# W108X.net
KiCad netlist of a schematic drawn in EAGLE
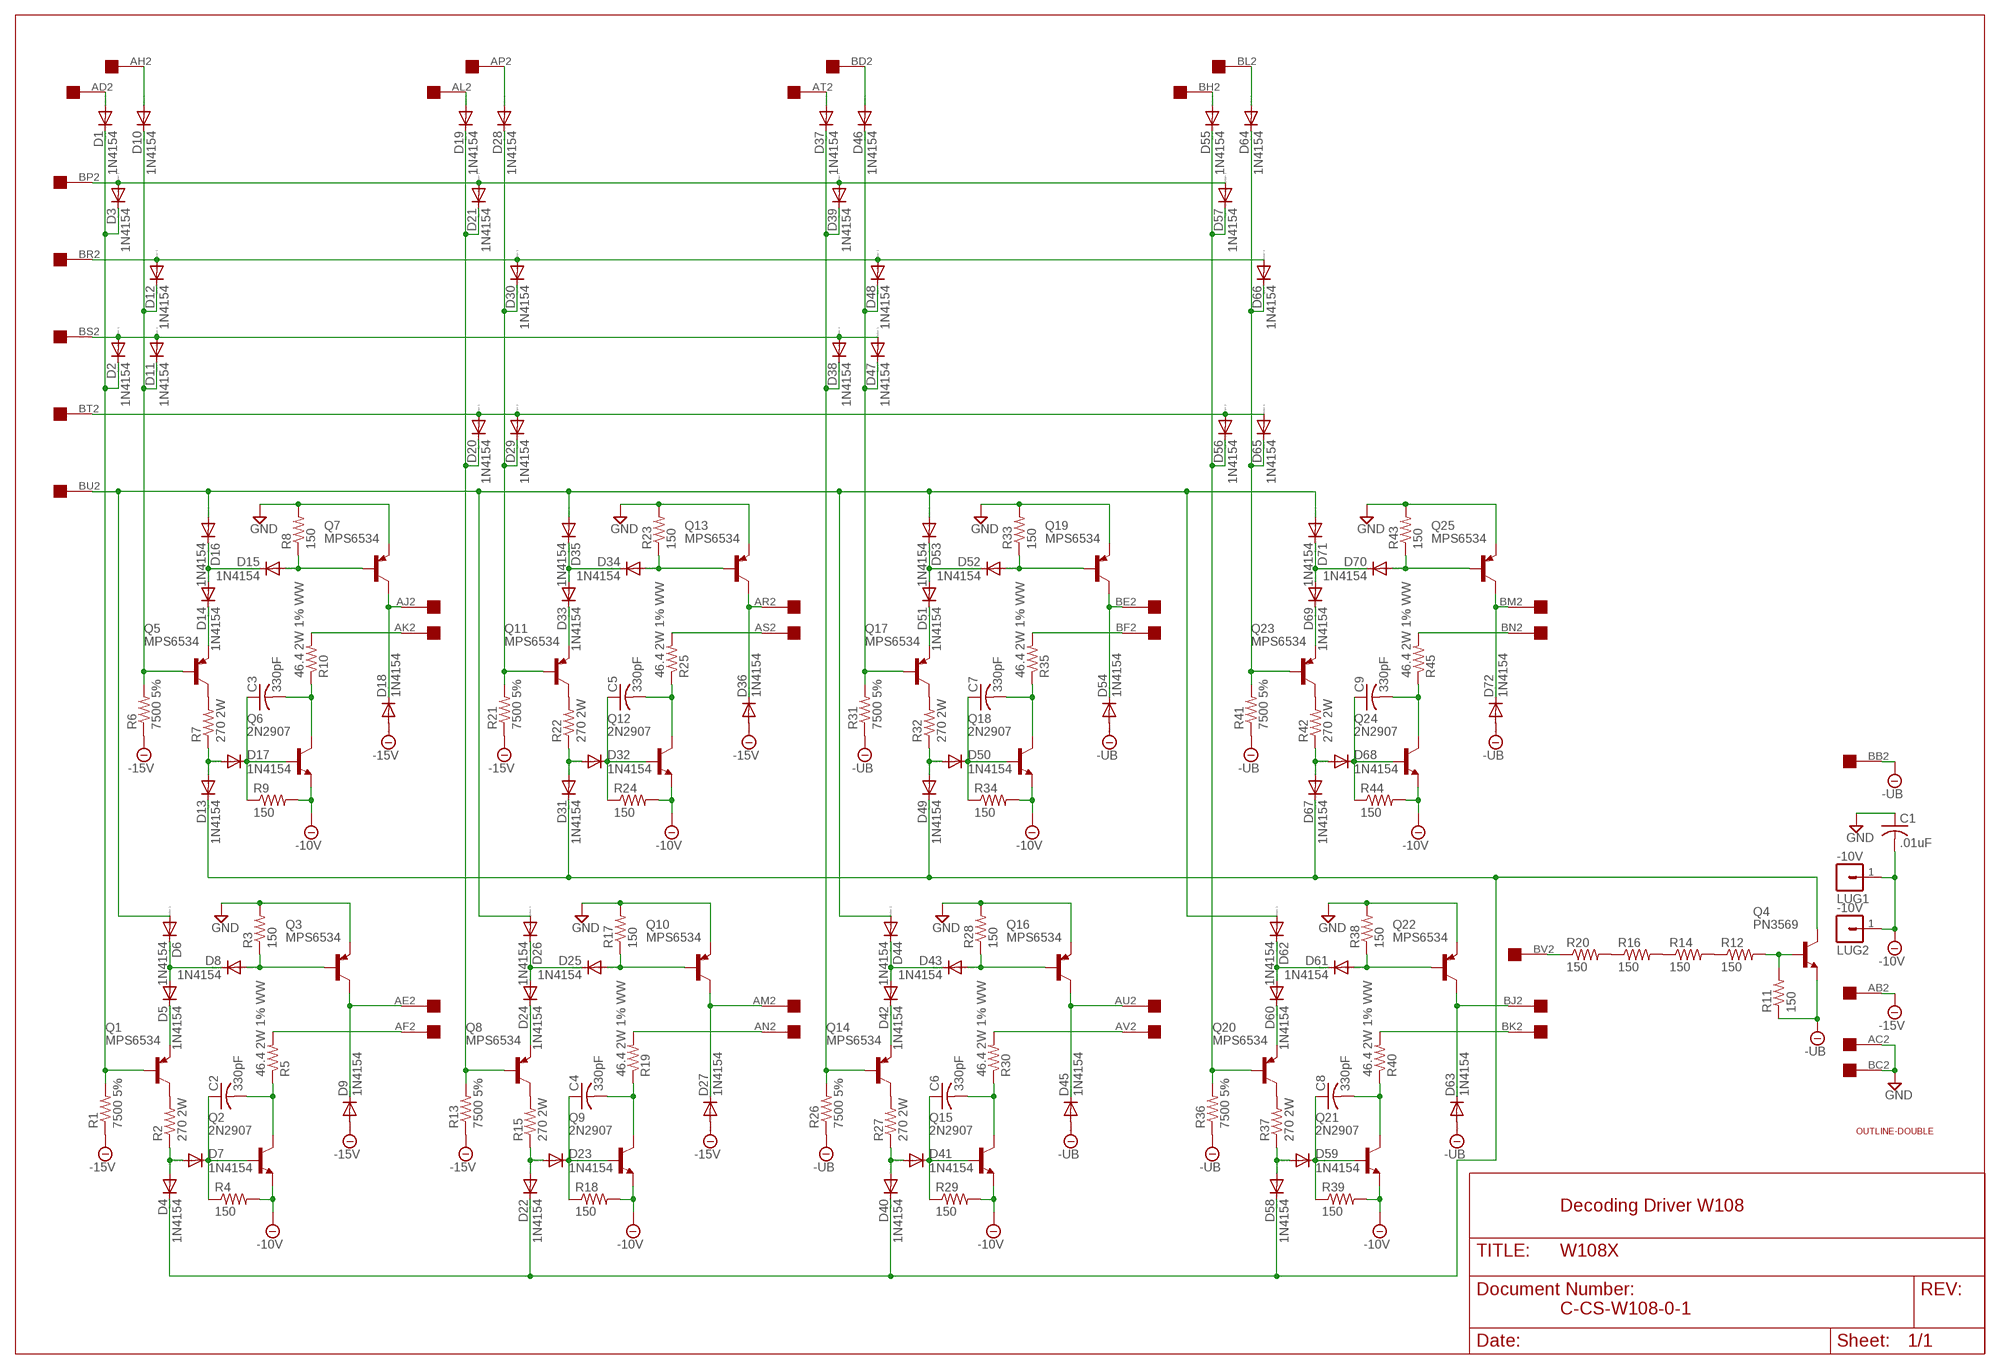
[diagram p0: schematic, sheet 1]

(export (version "E")
  (design (tool "Eeschema 10.0.6"))
  (components
    (comp (ref "C1")
      (value ".01uF")
      (footprint "eagle-import:C075-032X103")
      (libsource (lib "eagle-import") (part "C-US075-032X103"))
    )
    (comp (ref "C2")
      (value "330pF")
      (footprint "eagle-import:C075-032X103")
      (libsource (lib "eagle-import") (part "C-US075-032X103"))
    )
    (comp (ref "C3")
      (value "330pF")
      (footprint "eagle-import:C075-032X103")
      (libsource (lib "eagle-import") (part "C-US075-032X103"))
    )
    (comp (ref "C4")
      (value "330pF")
      (footprint "eagle-import:C075-032X103")
      (libsource (lib "eagle-import") (part "C-US075-032X103"))
    )
    (comp (ref "C5")
      (value "330pF")
      (footprint "eagle-import:C075-032X103")
      (libsource (lib "eagle-import") (part "C-US075-032X103"))
    )
    (comp (ref "C6")
      (value "330pF")
      (footprint "eagle-import:C075-032X103")
      (libsource (lib "eagle-import") (part "C-US075-032X103"))
    )
    (comp (ref "C7")
      (value "330pF")
      (footprint "eagle-import:C075-032X103")
      (libsource (lib "eagle-import") (part "C-US075-032X103"))
    )
    (comp (ref "C8")
      (value "330pF")
      (footprint "eagle-import:C075-032X103")
      (libsource (lib "eagle-import") (part "C-US075-032X103"))
    )
    (comp (ref "C9")
      (value "330pF")
      (footprint "eagle-import:C075-032X103")
      (libsource (lib "eagle-import") (part "C-US075-032X103"))
    )
    (comp (ref "D1")
      (value "1N4154")
      (footprint "eagle-import:DO35-10")
      (libsource (lib "eagle-import") (part "1N4148DO35-10"))
    )
    (comp (ref "D2")
      (value "1N4154")
      (footprint "eagle-import:DO35-10")
      (libsource (lib "eagle-import") (part "1N4148DO35-10"))
    )
    (comp (ref "D3")
      (value "1N4154")
      (footprint "eagle-import:DO35-10")
      (libsource (lib "eagle-import") (part "1N4148DO35-10"))
    )
    (comp (ref "D4")
      (value "1N4154")
      (footprint "eagle-import:DO35-10")
      (libsource (lib "eagle-import") (part "1N4148DO35-10"))
    )
    (comp (ref "D5")
      (value "1N4154")
      (footprint "eagle-import:DO35-10")
      (libsource (lib "eagle-import") (part "1N4148DO35-10"))
    )
    (comp (ref "D6")
      (value "1N4154")
      (footprint "eagle-import:DO35-10")
      (libsource (lib "eagle-import") (part "1N4148DO35-10"))
    )
    (comp (ref "D7")
      (value "1N4154")
      (footprint "eagle-import:DO35-10")
      (libsource (lib "eagle-import") (part "1N4148DO35-10"))
    )
    (comp (ref "D8")
      (value "1N4154")
      (footprint "eagle-import:DO35-10")
      (libsource (lib "eagle-import") (part "1N4148DO35-10"))
    )
    (comp (ref "D9")
      (value "1N4154")
      (footprint "eagle-import:DO35-10")
      (libsource (lib "eagle-import") (part "1N4148DO35-10"))
    )
    (comp (ref "D10")
      (value "1N4154")
      (footprint "eagle-import:DO35-10")
      (libsource (lib "eagle-import") (part "1N4148DO35-10"))
    )
    (comp (ref "D11")
      (value "1N4154")
      (footprint "eagle-import:DO35-10")
      (libsource (lib "eagle-import") (part "1N4148DO35-10"))
    )
    (comp (ref "D12")
      (value "1N4154")
      (footprint "eagle-import:DO35-10")
      (libsource (lib "eagle-import") (part "1N4148DO35-10"))
    )
    (comp (ref "D13")
      (value "1N4154")
      (footprint "eagle-import:DO35-10")
      (libsource (lib "eagle-import") (part "1N4148DO35-10"))
    )
    (comp (ref "D14")
      (value "1N4154")
      (footprint "eagle-import:DO35-10")
      (libsource (lib "eagle-import") (part "1N4148DO35-10"))
    )
    (comp (ref "D15")
      (value "1N4154")
      (footprint "eagle-import:DO35-10")
      (libsource (lib "eagle-import") (part "1N4148DO35-10"))
    )
    (comp (ref "D16")
      (value "1N4154")
      (footprint "eagle-import:DO35-10")
      (libsource (lib "eagle-import") (part "1N4148DO35-10"))
    )
    (comp (ref "D17")
      (value "1N4154")
      (footprint "eagle-import:DO35-10")
      (libsource (lib "eagle-import") (part "1N4148DO35-10"))
    )
    (comp (ref "D18")
      (value "1N4154")
      (footprint "eagle-import:DO35-10")
      (libsource (lib "eagle-import") (part "1N4148DO35-10"))
    )
    (comp (ref "D19")
      (value "1N4154")
      (footprint "eagle-import:DO35-10")
      (libsource (lib "eagle-import") (part "1N4148DO35-10"))
    )
    (comp (ref "D20")
      (value "1N4154")
      (footprint "eagle-import:DO35-10")
      (libsource (lib "eagle-import") (part "1N4148DO35-10"))
    )
    (comp (ref "D21")
      (value "1N4154")
      (footprint "eagle-import:DO35-10")
      (libsource (lib "eagle-import") (part "1N4148DO35-10"))
    )
    (comp (ref "D22")
      (value "1N4154")
      (footprint "eagle-import:DO35-10")
      (libsource (lib "eagle-import") (part "1N4148DO35-10"))
    )
    (comp (ref "D23")
      (value "1N4154")
      (footprint "eagle-import:DO35-10")
      (libsource (lib "eagle-import") (part "1N4148DO35-10"))
    )
    (comp (ref "D24")
      (value "1N4154")
      (footprint "eagle-import:DO35-10")
      (libsource (lib "eagle-import") (part "1N4148DO35-10"))
    )
    (comp (ref "D25")
      (value "1N4154")
      (footprint "eagle-import:DO35-10")
      (libsource (lib "eagle-import") (part "1N4148DO35-10"))
    )
    (comp (ref "D26")
      (value "1N4154")
      (footprint "eagle-import:DO35-10")
      (libsource (lib "eagle-import") (part "1N4148DO35-10"))
    )
    (comp (ref "D27")
      (value "1N4154")
      (footprint "eagle-import:DO35-10")
      (libsource (lib "eagle-import") (part "1N4148DO35-10"))
    )
    (comp (ref "D28")
      (value "1N4154")
      (footprint "eagle-import:DO35-10")
      (libsource (lib "eagle-import") (part "1N4148DO35-10"))
    )
    (comp (ref "D29")
      (value "1N4154")
      (footprint "eagle-import:DO35-10")
      (libsource (lib "eagle-import") (part "1N4148DO35-10"))
    )
    (comp (ref "D30")
      (value "1N4154")
      (footprint "eagle-import:DO35-10")
      (libsource (lib "eagle-import") (part "1N4148DO35-10"))
    )
    (comp (ref "D31")
      (value "1N4154")
      (footprint "eagle-import:DO35-10")
      (libsource (lib "eagle-import") (part "1N4148DO35-10"))
    )
    (comp (ref "D32")
      (value "1N4154")
      (footprint "eagle-import:DO35-10")
      (libsource (lib "eagle-import") (part "1N4148DO35-10"))
    )
    (comp (ref "D33")
      (value "1N4154")
      (footprint "eagle-import:DO35-10")
      (libsource (lib "eagle-import") (part "1N4148DO35-10"))
    )
    (comp (ref "D34")
      (value "1N4154")
      (footprint "eagle-import:DO35-10")
      (libsource (lib "eagle-import") (part "1N4148DO35-10"))
    )
    (comp (ref "D35")
      (value "1N4154")
      (footprint "eagle-import:DO35-10")
      (libsource (lib "eagle-import") (part "1N4148DO35-10"))
    )
    (comp (ref "D36")
      (value "1N4154")
      (footprint "eagle-import:DO35-10")
      (libsource (lib "eagle-import") (part "1N4148DO35-10"))
    )
    (comp (ref "D37")
      (value "1N4154")
      (footprint "eagle-import:DO35-10")
      (libsource (lib "eagle-import") (part "1N4148DO35-10"))
    )
    (comp (ref "D38")
      (value "1N4154")
      (footprint "eagle-import:DO35-10")
      (libsource (lib "eagle-import") (part "1N4148DO35-10"))
    )
    (comp (ref "D39")
      (value "1N4154")
      (footprint "eagle-import:DO35-10")
      (libsource (lib "eagle-import") (part "1N4148DO35-10"))
    )
    (comp (ref "D40")
      (value "1N4154")
      (footprint "eagle-import:DO35-10")
      (libsource (lib "eagle-import") (part "1N4148DO35-10"))
    )
    (comp (ref "D41")
      (value "1N4154")
      (footprint "eagle-import:DO35-10")
      (libsource (lib "eagle-import") (part "1N4148DO35-10"))
    )
    (comp (ref "D42")
      (value "1N4154")
      (footprint "eagle-import:DO35-10")
      (libsource (lib "eagle-import") (part "1N4148DO35-10"))
    )
    (comp (ref "D43")
      (value "1N4154")
      (footprint "eagle-import:DO35-10")
      (libsource (lib "eagle-import") (part "1N4148DO35-10"))
    )
    (comp (ref "D44")
      (value "1N4154")
      (footprint "eagle-import:DO35-10")
      (libsource (lib "eagle-import") (part "1N4148DO35-10"))
    )
    (comp (ref "D45")
      (value "1N4154")
      (footprint "eagle-import:DO35-10")
      (libsource (lib "eagle-import") (part "1N4148DO35-10"))
    )
    (comp (ref "D46")
      (value "1N4154")
      (footprint "eagle-import:DO35-10")
      (libsource (lib "eagle-import") (part "1N4148DO35-10"))
    )
    (comp (ref "D47")
      (value "1N4154")
      (footprint "eagle-import:DO35-10")
      (libsource (lib "eagle-import") (part "1N4148DO35-10"))
    )
    (comp (ref "D48")
      (value "1N4154")
      (footprint "eagle-import:DO35-10")
      (libsource (lib "eagle-import") (part "1N4148DO35-10"))
    )
    (comp (ref "D49")
      (value "1N4154")
      (footprint "eagle-import:DO35-10")
      (libsource (lib "eagle-import") (part "1N4148DO35-10"))
    )
    (comp (ref "D50")
      (value "1N4154")
      (footprint "eagle-import:DO35-10")
      (libsource (lib "eagle-import") (part "1N4148DO35-10"))
    )
    (comp (ref "D51")
      (value "1N4154")
      (footprint "eagle-import:DO35-10")
      (libsource (lib "eagle-import") (part "1N4148DO35-10"))
    )
    (comp (ref "D52")
      (value "1N4154")
      (footprint "eagle-import:DO35-10")
      (libsource (lib "eagle-import") (part "1N4148DO35-10"))
    )
    (comp (ref "D53")
      (value "1N4154")
      (footprint "eagle-import:DO35-10")
      (libsource (lib "eagle-import") (part "1N4148DO35-10"))
    )
    (comp (ref "D54")
      (value "1N4154")
      (footprint "eagle-import:DO35-10")
      (libsource (lib "eagle-import") (part "1N4148DO35-10"))
    )
    (comp (ref "D55")
      (value "1N4154")
      (footprint "eagle-import:DO35-10")
      (libsource (lib "eagle-import") (part "1N4148DO35-10"))
    )
    (comp (ref "D56")
      (value "1N4154")
      (footprint "eagle-import:DO35-10")
      (libsource (lib "eagle-import") (part "1N4148DO35-10"))
    )
    (comp (ref "D57")
      (value "1N4154")
      (footprint "eagle-import:DO35-10")
      (libsource (lib "eagle-import") (part "1N4148DO35-10"))
    )
    (comp (ref "D58")
      (value "1N4154")
      (footprint "eagle-import:DO35-10")
      (libsource (lib "eagle-import") (part "1N4148DO35-10"))
    )
    (comp (ref "D59")
      (value "1N4154")
      (footprint "eagle-import:DO35-10")
      (libsource (lib "eagle-import") (part "1N4148DO35-10"))
    )
    (comp (ref "D60")
      (value "1N4154")
      (footprint "eagle-import:DO35-10")
      (libsource (lib "eagle-import") (part "1N4148DO35-10"))
    )
    (comp (ref "D61")
      (value "1N4154")
      (footprint "eagle-import:DO35-10")
      (libsource (lib "eagle-import") (part "1N4148DO35-10"))
    )
    (comp (ref "D62")
      (value "1N4154")
      (footprint "eagle-import:DO35-10")
      (libsource (lib "eagle-import") (part "1N4148DO35-10"))
    )
    (comp (ref "D63")
      (value "1N4154")
      (footprint "eagle-import:DO35-10")
      (libsource (lib "eagle-import") (part "1N4148DO35-10"))
    )
    (comp (ref "D64")
      (value "1N4154")
      (footprint "eagle-import:DO35-10")
      (libsource (lib "eagle-import") (part "1N4148DO35-10"))
    )
    (comp (ref "D65")
      (value "1N4154")
      (footprint "eagle-import:DO35-10")
      (libsource (lib "eagle-import") (part "1N4148DO35-10"))
    )
    (comp (ref "D66")
      (value "1N4154")
      (footprint "eagle-import:DO35-10")
      (libsource (lib "eagle-import") (part "1N4148DO35-10"))
    )
    (comp (ref "D67")
      (value "1N4154")
      (footprint "eagle-import:DO35-10")
      (libsource (lib "eagle-import") (part "1N4148DO35-10"))
    )
    (comp (ref "D68")
      (value "1N4154")
      (footprint "eagle-import:DO35-10")
      (libsource (lib "eagle-import") (part "1N4148DO35-10"))
    )
    (comp (ref "D69")
      (value "1N4154")
      (footprint "eagle-import:DO35-10")
      (libsource (lib "eagle-import") (part "1N4148DO35-10"))
    )
    (comp (ref "D70")
      (value "1N4154")
      (footprint "eagle-import:DO35-10")
      (libsource (lib "eagle-import") (part "1N4148DO35-10"))
    )
    (comp (ref "D71")
      (value "1N4154")
      (footprint "eagle-import:DO35-10")
      (libsource (lib "eagle-import") (part "1N4148DO35-10"))
    )
    (comp (ref "D72")
      (value "1N4154")
      (footprint "eagle-import:DO35-10")
      (libsource (lib "eagle-import") (part "1N4148DO35-10"))
    )
    (comp (ref "LUG1")
      (value "-10V")
      (footprint "eagle-import:SPADELUG")
      (libsource (lib "eagle-import") (part "LUG"))
    )
    (comp (ref "LUG2")
      (value "-10V")
      (footprint "eagle-import:SPADELUG")
      (libsource (lib "eagle-import") (part "LUG"))
    )
    (comp (ref "Q1")
      (value "MPS6534")
      (footprint "eagle-import:TO39")
      (libsource (lib "eagle-import") (part "2N2904"))
    )
    (comp (ref "Q2")
      (value "2N2907")
      (footprint "eagle-import:TO5")
      (libsource (lib "eagle-import") (part "2N2102"))
    )
    (comp (ref "Q3")
      (value "MPS6534")
      (footprint "eagle-import:TO39")
      (libsource (lib "eagle-import") (part "2N2904"))
    )
    (comp (ref "Q4")
      (value "PN3569")
      (footprint "eagle-import:TO5")
      (libsource (lib "eagle-import") (part "2N2102"))
    )
    (comp (ref "Q5")
      (value "MPS6534")
      (footprint "eagle-import:TO39")
      (libsource (lib "eagle-import") (part "2N2904"))
    )
    (comp (ref "Q6")
      (value "2N2907")
      (footprint "eagle-import:TO5")
      (libsource (lib "eagle-import") (part "2N2102"))
    )
    (comp (ref "Q7")
      (value "MPS6534")
      (footprint "eagle-import:TO39")
      (libsource (lib "eagle-import") (part "2N2904"))
    )
    (comp (ref "Q8")
      (value "MPS6534")
      (footprint "eagle-import:TO39")
      (libsource (lib "eagle-import") (part "2N2904"))
    )
    (comp (ref "Q9")
      (value "2N2907")
      (footprint "eagle-import:TO5")
      (libsource (lib "eagle-import") (part "2N2102"))
    )
    (comp (ref "Q10")
      (value "MPS6534")
      (footprint "eagle-import:TO39")
      (libsource (lib "eagle-import") (part "2N2904"))
    )
    (comp (ref "Q11")
      (value "MPS6534")
      (footprint "eagle-import:TO39")
      (libsource (lib "eagle-import") (part "2N2904"))
    )
    (comp (ref "Q12")
      (value "2N2907")
      (footprint "eagle-import:TO5")
      (libsource (lib "eagle-import") (part "2N2102"))
    )
    (comp (ref "Q13")
      (value "MPS6534")
      (footprint "eagle-import:TO39")
      (libsource (lib "eagle-import") (part "2N2904"))
    )
    (comp (ref "Q14")
      (value "MPS6534")
      (footprint "eagle-import:TO39")
      (libsource (lib "eagle-import") (part "2N2904"))
    )
    (comp (ref "Q15")
      (value "2N2907")
      (footprint "eagle-import:TO5")
      (libsource (lib "eagle-import") (part "2N2102"))
    )
    (comp (ref "Q16")
      (value "MPS6534")
      (footprint "eagle-import:TO39")
      (libsource (lib "eagle-import") (part "2N2904"))
    )
    (comp (ref "Q17")
      (value "MPS6534")
      (footprint "eagle-import:TO39")
      (libsource (lib "eagle-import") (part "2N2904"))
    )
    (comp (ref "Q18")
      (value "2N2907")
      (footprint "eagle-import:TO5")
      (libsource (lib "eagle-import") (part "2N2102"))
    )
    (comp (ref "Q19")
      (value "MPS6534")
      (footprint "eagle-import:TO39")
      (libsource (lib "eagle-import") (part "2N2904"))
    )
    (comp (ref "Q20")
      (value "MPS6534")
      (footprint "eagle-import:TO39")
      (libsource (lib "eagle-import") (part "2N2904"))
    )
    (comp (ref "Q21")
      (value "2N2907")
      (footprint "eagle-import:TO5")
      (libsource (lib "eagle-import") (part "2N2102"))
    )
    (comp (ref "Q22")
      (value "MPS6534")
      (footprint "eagle-import:TO39")
      (libsource (lib "eagle-import") (part "2N2904"))
    )
    (comp (ref "Q23")
      (value "MPS6534")
      (footprint "eagle-import:TO39")
      (libsource (lib "eagle-import") (part "2N2904"))
    )
    (comp (ref "Q24")
      (value "2N2907")
      (footprint "eagle-import:TO5")
      (libsource (lib "eagle-import") (part "2N2102"))
    )
    (comp (ref "Q25")
      (value "MPS6534")
      (footprint "eagle-import:TO39")
      (libsource (lib "eagle-import") (part "2N2904"))
    )
    (comp (ref "R1")
      (value "7500 5%")
      (footprint "eagle-import:0207_10")
      (libsource (lib "eagle-import") (part "R-US_0207/10"))
    )
    (comp (ref "R2")
      (value "270 2W")
      (footprint "eagle-import:0617_22")
      (libsource (lib "eagle-import") (part "R-US_0617/22"))
    )
    (comp (ref "R3")
      (value "150")
      (footprint "eagle-import:0207_10")
      (libsource (lib "eagle-import") (part "R-US_0207/10"))
    )
    (comp (ref "R4")
      (value "150")
      (footprint "eagle-import:0207_10")
      (libsource (lib "eagle-import") (part "R-US_0207/10"))
    )
    (comp (ref "R5")
      (value "46.4 2W 1% WW")
      (footprint "eagle-import:0414_20")
      (libsource (lib "eagle-import") (part "R-US_0414/20"))
    )
    (comp (ref "R6")
      (value "7500 5%")
      (footprint "eagle-import:0207_10")
      (libsource (lib "eagle-import") (part "R-US_0207/10"))
    )
    (comp (ref "R7")
      (value "270 2W")
      (footprint "eagle-import:0617_22")
      (libsource (lib "eagle-import") (part "R-US_0617/22"))
    )
    (comp (ref "R8")
      (value "150")
      (footprint "eagle-import:0207_10")
      (libsource (lib "eagle-import") (part "R-US_0207/10"))
    )
    (comp (ref "R9")
      (value "150")
      (footprint "eagle-import:0207_10")
      (libsource (lib "eagle-import") (part "R-US_0207/10"))
    )
    (comp (ref "R10")
      (value "46.4 2W 1% WW")
      (footprint "eagle-import:0414_20")
      (libsource (lib "eagle-import") (part "R-US_0414/20"))
    )
    (comp (ref "R11")
      (value "150")
      (footprint "eagle-import:0207_10")
      (libsource (lib "eagle-import") (part "R-US_0207/10"))
    )
    (comp (ref "R12")
      (value "150")
      (footprint "eagle-import:0207_10")
      (libsource (lib "eagle-import") (part "R-US_0207/10"))
    )
    (comp (ref "R13")
      (value "7500 5%")
      (footprint "eagle-import:0207_10")
      (libsource (lib "eagle-import") (part "R-US_0207/10"))
    )
    (comp (ref "R14")
      (value "150")
      (footprint "eagle-import:0207_10")
      (libsource (lib "eagle-import") (part "R-US_0207/10"))
    )
    (comp (ref "R15")
      (value "270 2W")
      (footprint "eagle-import:0617_22")
      (libsource (lib "eagle-import") (part "R-US_0617/22"))
    )
    (comp (ref "R16")
      (value "150")
      (footprint "eagle-import:0207_10")
      (libsource (lib "eagle-import") (part "R-US_0207/10"))
    )
    (comp (ref "R17")
      (value "150")
      (footprint "eagle-import:0207_10")
      (libsource (lib "eagle-import") (part "R-US_0207/10"))
    )
    (comp (ref "R18")
      (value "150")
      (footprint "eagle-import:0207_10")
      (libsource (lib "eagle-import") (part "R-US_0207/10"))
    )
    (comp (ref "R19")
      (value "46.4 2W 1% WW")
      (footprint "eagle-import:0414_20")
      (libsource (lib "eagle-import") (part "R-US_0414/20"))
    )
    (comp (ref "R20")
      (value "150")
      (footprint "eagle-import:0207_10")
      (libsource (lib "eagle-import") (part "R-US_0207/10"))
    )
    (comp (ref "R21")
      (value "7500 5%")
      (footprint "eagle-import:0207_10")
      (libsource (lib "eagle-import") (part "R-US_0207/10"))
    )
    (comp (ref "R22")
      (value "270 2W")
      (footprint "eagle-import:0617_22")
      (libsource (lib "eagle-import") (part "R-US_0617/22"))
    )
    (comp (ref "R23")
      (value "150")
      (footprint "eagle-import:0207_10")
      (libsource (lib "eagle-import") (part "R-US_0207/10"))
    )
    (comp (ref "R24")
      (value "150")
      (footprint "eagle-import:0207_10")
      (libsource (lib "eagle-import") (part "R-US_0207/10"))
    )
    (comp (ref "R25")
      (value "46.4 2W 1% WW")
      (footprint "eagle-import:0414_20")
      (libsource (lib "eagle-import") (part "R-US_0414/20"))
    )
    (comp (ref "R26")
      (value "7500 5%")
      (footprint "eagle-import:0207_10")
      (libsource (lib "eagle-import") (part "R-US_0207/10"))
    )
    (comp (ref "R27")
      (value "270 2W")
      (footprint "eagle-import:0617_22")
      (libsource (lib "eagle-import") (part "R-US_0617/22"))
    )
    (comp (ref "R28")
      (value "150")
      (footprint "eagle-import:0207_10")
      (libsource (lib "eagle-import") (part "R-US_0207/10"))
    )
    (comp (ref "R29")
      (value "150")
      (footprint "eagle-import:0207_10")
      (libsource (lib "eagle-import") (part "R-US_0207/10"))
    )
    (comp (ref "R30")
      (value "46.4 2W 1% WW")
      (footprint "eagle-import:0414_20")
      (libsource (lib "eagle-import") (part "R-US_0414/20"))
    )
    (comp (ref "R31")
      (value "7500 5%")
      (footprint "eagle-import:0207_10")
      (libsource (lib "eagle-import") (part "R-US_0207/10"))
    )
    (comp (ref "R32")
      (value "270 2W")
      (footprint "eagle-import:0617_22")
      (libsource (lib "eagle-import") (part "R-US_0617/22"))
    )
    (comp (ref "R33")
      (value "150")
      (footprint "eagle-import:0207_10")
      (libsource (lib "eagle-import") (part "R-US_0207/10"))
    )
    (comp (ref "R34")
      (value "150")
      (footprint "eagle-import:0207_10")
      (libsource (lib "eagle-import") (part "R-US_0207/10"))
    )
    (comp (ref "R35")
      (value "46.4 2W 1% WW")
      (footprint "eagle-import:0414_20")
      (libsource (lib "eagle-import") (part "R-US_0414/20"))
    )
    (comp (ref "R36")
      (value "7500 5%")
      (footprint "eagle-import:0207_10")
      (libsource (lib "eagle-import") (part "R-US_0207/10"))
    )
    (comp (ref "R37")
      (value "270 2W")
      (footprint "eagle-import:0617_22")
      (libsource (lib "eagle-import") (part "R-US_0617/22"))
    )
    (comp (ref "R38")
      (value "150")
      (footprint "eagle-import:0207_10")
      (libsource (lib "eagle-import") (part "R-US_0207/10"))
    )
    (comp (ref "R39")
      (value "150")
      (footprint "eagle-import:0207_10")
      (libsource (lib "eagle-import") (part "R-US_0207/10"))
    )
    (comp (ref "R40")
      (value "46.4 2W 1% WW")
      (footprint "eagle-import:0414_20")
      (libsource (lib "eagle-import") (part "R-US_0414/20"))
    )
    (comp (ref "R41")
      (value "7500 5%")
      (footprint "eagle-import:0207_10")
      (libsource (lib "eagle-import") (part "R-US_0207/10"))
    )
    (comp (ref "R42")
      (value "270 2W")
      (footprint "eagle-import:0617_22")
      (libsource (lib "eagle-import") (part "R-US_0617/22"))
    )
    (comp (ref "R43")
      (value "150")
      (footprint "eagle-import:0207_10")
      (libsource (lib "eagle-import") (part "R-US_0207/10"))
    )
    (comp (ref "R44")
      (value "150")
      (footprint "eagle-import:0207_10")
      (libsource (lib "eagle-import") (part "R-US_0207/10"))
    )
    (comp (ref "R45")
      (value "46.4 2W 1% WW")
      (footprint "eagle-import:0414_20")
      (libsource (lib "eagle-import") (part "R-US_0414/20"))
    )
    (comp (ref "U$1")
      (value "OUTLINE-DOUBLE")
      (footprint "eagle-import:DOUBLE")
      (libsource (lib "eagle-import") (part "OUTLINE-DOUBLE"))
    )
    (comp (ref "U$2")
      (value "DOUBLE")
      (footprint "eagle-import:EDGE-CON4")
      (libsource (lib "eagle-import") (part "DOUBLE"))
    )
  )
  (nets
    (net (code "1") (name "-10V") (class "Default")
      (node (ref "C1") (pin "2") (pinfunction "2_2") (pintype "passive"))
      (node (ref "LUG1") (pin "1") (pinfunction "1_1") (pintype "passive"))
      (node (ref "LUG2") (pin "1") (pinfunction "1_1") (pintype "passive"))
      (node (ref "Q12") (pin "1") (pinfunction "E_1") (pintype "passive"))
      (node (ref "Q15") (pin "1") (pinfunction "E_1") (pintype "passive"))
      (node (ref "Q18") (pin "1") (pinfunction "E_1") (pintype "passive"))
      (node (ref "Q2") (pin "1") (pinfunction "E_1") (pintype "passive"))
      (node (ref "Q21") (pin "1") (pinfunction "E_1") (pintype "passive"))
      (node (ref "Q24") (pin "1") (pinfunction "E_1") (pintype "passive"))
      (node (ref "Q6") (pin "1") (pinfunction "E_1") (pintype "passive"))
      (node (ref "Q9") (pin "1") (pinfunction "E_1") (pintype "passive"))
      (node (ref "R18") (pin "2") (pinfunction "2_2") (pintype "passive"))
      (node (ref "R24") (pin "2") (pinfunction "2_2") (pintype "passive"))
      (node (ref "R29") (pin "2") (pinfunction "2_2") (pintype "passive"))
      (node (ref "R34") (pin "2") (pinfunction "2_2") (pintype "passive"))
      (node (ref "R39") (pin "2") (pinfunction "2_2") (pintype "passive"))
      (node (ref "R4") (pin "2") (pinfunction "2_2") (pintype "passive"))
      (node (ref "R44") (pin "2") (pinfunction "2_2") (pintype "passive"))
      (node (ref "R9") (pin "2") (pinfunction "2_2") (pintype "passive"))
    )
    (net (code "2") (name "-15V") (class "Default")
      (node (ref "D18") (pin "A") (pinfunction "A_A") (pintype "passive"))
      (node (ref "D27") (pin "A") (pinfunction "A_A") (pintype "passive"))
      (node (ref "D36") (pin "A") (pinfunction "A_A") (pintype "passive"))
      (node (ref "D9") (pin "A") (pinfunction "A_A") (pintype "passive"))
      (node (ref "R1") (pin "1") (pinfunction "1_1") (pintype "passive"))
      (node (ref "R13") (pin "1") (pinfunction "1_1") (pintype "passive"))
      (node (ref "R21") (pin "1") (pinfunction "1_1") (pintype "passive"))
      (node (ref "R6") (pin "1") (pinfunction "1_1") (pintype "passive"))
      (node (ref "U$2") (pin "AB2") (pinfunction "1_AB2") (pintype "bidirectional"))
    )
    (net (code "3") (name "-UB") (class "Default")
      (node (ref "D45") (pin "A") (pinfunction "A_A") (pintype "passive"))
      (node (ref "D54") (pin "A") (pinfunction "A_A") (pintype "passive"))
      (node (ref "D63") (pin "A") (pinfunction "A_A") (pintype "passive"))
      (node (ref "D72") (pin "A") (pinfunction "A_A") (pintype "passive"))
      (node (ref "Q4") (pin "1") (pinfunction "E_1") (pintype "passive"))
      (node (ref "R11") (pin "1") (pinfunction "1_1") (pintype "passive"))
      (node (ref "R26") (pin "1") (pinfunction "1_1") (pintype "passive"))
      (node (ref "R31") (pin "1") (pinfunction "1_1") (pintype "passive"))
      (node (ref "R36") (pin "1") (pinfunction "1_1") (pintype "passive"))
      (node (ref "R41") (pin "1") (pinfunction "1_1") (pintype "passive"))
      (node (ref "U$2") (pin "BB2") (pinfunction "1_BB2") (pintype "bidirectional"))
    )
    (net (code "4") (name "GND") (class "Default")
      (node (ref "C1") (pin "1") (pinfunction "1_1") (pintype "passive"))
      (node (ref "Q10") (pin "1") (pinfunction "E_1") (pintype "passive"))
      (node (ref "Q13") (pin "1") (pinfunction "E_1") (pintype "passive"))
      (node (ref "Q16") (pin "1") (pinfunction "E_1") (pintype "passive"))
      (node (ref "Q19") (pin "1") (pinfunction "E_1") (pintype "passive"))
      (node (ref "Q22") (pin "1") (pinfunction "E_1") (pintype "passive"))
      (node (ref "Q25") (pin "1") (pinfunction "E_1") (pintype "passive"))
      (node (ref "Q3") (pin "1") (pinfunction "E_1") (pintype "passive"))
      (node (ref "Q7") (pin "1") (pinfunction "E_1") (pintype "passive"))
      (node (ref "R17") (pin "2") (pinfunction "2_2") (pintype "passive"))
      (node (ref "R23") (pin "2") (pinfunction "2_2") (pintype "passive"))
      (node (ref "R28") (pin "2") (pinfunction "2_2") (pintype "passive"))
      (node (ref "R3") (pin "2") (pinfunction "2_2") (pintype "passive"))
      (node (ref "R33") (pin "2") (pinfunction "2_2") (pintype "passive"))
      (node (ref "R38") (pin "2") (pinfunction "2_2") (pintype "passive"))
      (node (ref "R43") (pin "2") (pinfunction "2_2") (pintype "passive"))
      (node (ref "R8") (pin "2") (pinfunction "2_2") (pintype "passive"))
      (node (ref "U$2") (pin "AC2") (pinfunction "1_AC2") (pintype "bidirectional"))
      (node (ref "U$2") (pin "BC2") (pinfunction "1_BC2") (pintype "bidirectional"))
    )
    (net (code "5") (name "Net-(D4-PadA)") (class "Default")
      (node (ref "D4") (pin "A") (pinfunction "A_A") (pintype "passive"))
      (node (ref "D7") (pin "A") (pinfunction "A_A") (pintype "passive"))
      (node (ref "R2") (pin "1") (pinfunction "1_1") (pintype "passive"))
    )
    (net (code "6") (name "Net-(D5-PadA)") (class "Default")
      (node (ref "D5") (pin "A") (pinfunction "A_A") (pintype "passive"))
      (node (ref "D6") (pin "C") (pinfunction "C_C") (pintype "passive"))
      (node (ref "D8") (pin "C") (pinfunction "C_C") (pintype "passive"))
    )
    (net (code "7") (name "Net-(D13-PadA)") (class "Default")
      (node (ref "D13") (pin "A") (pinfunction "A_A") (pintype "passive"))
      (node (ref "D17") (pin "A") (pinfunction "A_A") (pintype "passive"))
      (node (ref "R7") (pin "1") (pinfunction "1_1") (pintype "passive"))
    )
    (net (code "8") (name "Net-(D14-PadA)") (class "Default")
      (node (ref "D14") (pin "A") (pinfunction "A_A") (pintype "passive"))
      (node (ref "D15") (pin "C") (pinfunction "C_C") (pintype "passive"))
      (node (ref "D16") (pin "C") (pinfunction "C_C") (pintype "passive"))
    )
    (net (code "9") (name "Net-(D22-PadA)") (class "Default")
      (node (ref "D22") (pin "A") (pinfunction "A_A") (pintype "passive"))
      (node (ref "D23") (pin "A") (pinfunction "A_A") (pintype "passive"))
      (node (ref "R15") (pin "1") (pinfunction "1_1") (pintype "passive"))
    )
    (net (code "10") (name "Net-(D24-PadA)") (class "Default")
      (node (ref "D24") (pin "A") (pinfunction "A_A") (pintype "passive"))
      (node (ref "D25") (pin "C") (pinfunction "C_C") (pintype "passive"))
      (node (ref "D26") (pin "C") (pinfunction "C_C") (pintype "passive"))
    )
    (net (code "11") (name "Net-(D31-PadA)") (class "Default")
      (node (ref "D31") (pin "A") (pinfunction "A_A") (pintype "passive"))
      (node (ref "D32") (pin "A") (pinfunction "A_A") (pintype "passive"))
      (node (ref "R22") (pin "1") (pinfunction "1_1") (pintype "passive"))
    )
    (net (code "12") (name "Net-(D33-PadA)") (class "Default")
      (node (ref "D33") (pin "A") (pinfunction "A_A") (pintype "passive"))
      (node (ref "D34") (pin "C") (pinfunction "C_C") (pintype "passive"))
      (node (ref "D35") (pin "C") (pinfunction "C_C") (pintype "passive"))
    )
    (net (code "13") (name "Net-(D40-PadA)") (class "Default")
      (node (ref "D40") (pin "A") (pinfunction "A_A") (pintype "passive"))
      (node (ref "D41") (pin "A") (pinfunction "A_A") (pintype "passive"))
      (node (ref "R27") (pin "1") (pinfunction "1_1") (pintype "passive"))
    )
    (net (code "14") (name "Net-(D42-PadA)") (class "Default")
      (node (ref "D42") (pin "A") (pinfunction "A_A") (pintype "passive"))
      (node (ref "D43") (pin "C") (pinfunction "C_C") (pintype "passive"))
      (node (ref "D44") (pin "C") (pinfunction "C_C") (pintype "passive"))
    )
    (net (code "15") (name "Net-(D49-PadA)") (class "Default")
      (node (ref "D49") (pin "A") (pinfunction "A_A") (pintype "passive"))
      (node (ref "D50") (pin "A") (pinfunction "A_A") (pintype "passive"))
      (node (ref "R32") (pin "1") (pinfunction "1_1") (pintype "passive"))
    )
    (net (code "16") (name "Net-(D51-PadA)") (class "Default")
      (node (ref "D51") (pin "A") (pinfunction "A_A") (pintype "passive"))
      (node (ref "D52") (pin "C") (pinfunction "C_C") (pintype "passive"))
      (node (ref "D53") (pin "C") (pinfunction "C_C") (pintype "passive"))
    )
    (net (code "17") (name "Net-(D58-PadA)") (class "Default")
      (node (ref "D58") (pin "A") (pinfunction "A_A") (pintype "passive"))
      (node (ref "D59") (pin "A") (pinfunction "A_A") (pintype "passive"))
      (node (ref "R37") (pin "1") (pinfunction "1_1") (pintype "passive"))
    )
    (net (code "18") (name "Net-(D60-PadA)") (class "Default")
      (node (ref "D60") (pin "A") (pinfunction "A_A") (pintype "passive"))
      (node (ref "D61") (pin "C") (pinfunction "C_C") (pintype "passive"))
      (node (ref "D62") (pin "C") (pinfunction "C_C") (pintype "passive"))
    )
    (net (code "19") (name "Net-(D67-PadA)") (class "Default")
      (node (ref "D67") (pin "A") (pinfunction "A_A") (pintype "passive"))
      (node (ref "D68") (pin "A") (pinfunction "A_A") (pintype "passive"))
      (node (ref "R42") (pin "1") (pinfunction "1_1") (pintype "passive"))
    )
    (net (code "20") (name "Net-(D69-PadA)") (class "Default")
      (node (ref "D69") (pin "A") (pinfunction "A_A") (pintype "passive"))
      (node (ref "D70") (pin "C") (pinfunction "C_C") (pintype "passive"))
      (node (ref "D71") (pin "C") (pinfunction "C_C") (pintype "passive"))
    )
    (net (code "21") (name "Net-(Q1-B)") (class "Default")
      (node (ref "D1") (pin "C") (pinfunction "C_C") (pintype "passive"))
      (node (ref "D2") (pin "C") (pinfunction "C_C") (pintype "passive"))
      (node (ref "D3") (pin "C") (pinfunction "C_C") (pintype "passive"))
      (node (ref "Q1") (pin "2") (pinfunction "B_2") (pintype "passive"))
      (node (ref "R1") (pin "2") (pinfunction "2_2") (pintype "passive"))
    )
    (net (code "22") (name "Net-(Q1-C)") (class "Default")
      (node (ref "Q1") (pin "3") (pinfunction "C_3") (pintype "passive"))
      (node (ref "R2") (pin "2") (pinfunction "2_2") (pintype "passive"))
    )
    (net (code "23") (name "Net-(Q1-E)") (class "Default")
      (node (ref "D5") (pin "C") (pinfunction "C_C") (pintype "passive"))
      (node (ref "Q1") (pin "1") (pinfunction "E_1") (pintype "passive"))
    )
    (net (code "24") (name "Net-(Q2-B)") (class "Default")
      (node (ref "C2") (pin "1") (pinfunction "1_1") (pintype "passive"))
      (node (ref "D7") (pin "C") (pinfunction "C_C") (pintype "passive"))
      (node (ref "Q2") (pin "2") (pinfunction "B_2") (pintype "passive"))
      (node (ref "R4") (pin "1") (pinfunction "1_1") (pintype "passive"))
    )
    (net (code "25") (name "Net-(Q2-C)") (class "Default")
      (node (ref "C2") (pin "2") (pinfunction "2_2") (pintype "passive"))
      (node (ref "Q2") (pin "3") (pinfunction "C_3") (pintype "passive"))
      (node (ref "R5") (pin "1") (pinfunction "1_1") (pintype "passive"))
    )
    (net (code "26") (name "Net-(Q3-B)") (class "Default")
      (node (ref "D8") (pin "A") (pinfunction "A_A") (pintype "passive"))
      (node (ref "Q3") (pin "2") (pinfunction "B_2") (pintype "passive"))
      (node (ref "R3") (pin "1") (pinfunction "1_1") (pintype "passive"))
    )
    (net (code "27") (name "Net-(Q3-C)") (class "Default")
      (node (ref "D9") (pin "C") (pinfunction "C_C") (pintype "passive"))
      (node (ref "Q3") (pin "3") (pinfunction "C_3") (pintype "passive"))
      (node (ref "U$2") (pin "AE2") (pinfunction "1_AE2") (pintype "bidirectional"))
    )
    (net (code "28") (name "Net-(Q4-B)") (class "Default")
      (node (ref "Q4") (pin "2") (pinfunction "B_2") (pintype "passive"))
      (node (ref "R11") (pin "2") (pinfunction "2_2") (pintype "passive"))
      (node (ref "R12") (pin "2") (pinfunction "2_2") (pintype "passive"))
    )
    (net (code "29") (name "Net-(Q4-C)") (class "Default")
      (node (ref "D13") (pin "C") (pinfunction "C_C") (pintype "passive"))
      (node (ref "D22") (pin "C") (pinfunction "C_C") (pintype "passive"))
      (node (ref "D31") (pin "C") (pinfunction "C_C") (pintype "passive"))
      (node (ref "D4") (pin "C") (pinfunction "C_C") (pintype "passive"))
      (node (ref "D40") (pin "C") (pinfunction "C_C") (pintype "passive"))
      (node (ref "D49") (pin "C") (pinfunction "C_C") (pintype "passive"))
      (node (ref "D58") (pin "C") (pinfunction "C_C") (pintype "passive"))
      (node (ref "D67") (pin "C") (pinfunction "C_C") (pintype "passive"))
      (node (ref "Q4") (pin "3") (pinfunction "C_3") (pintype "passive"))
    )
    (net (code "30") (name "Net-(Q5-B)") (class "Default")
      (node (ref "D10") (pin "C") (pinfunction "C_C") (pintype "passive"))
      (node (ref "D11") (pin "C") (pinfunction "C_C") (pintype "passive"))
      (node (ref "D12") (pin "C") (pinfunction "C_C") (pintype "passive"))
      (node (ref "Q5") (pin "2") (pinfunction "B_2") (pintype "passive"))
      (node (ref "R6") (pin "2") (pinfunction "2_2") (pintype "passive"))
    )
    (net (code "31") (name "Net-(Q5-C)") (class "Default")
      (node (ref "Q5") (pin "3") (pinfunction "C_3") (pintype "passive"))
      (node (ref "R7") (pin "2") (pinfunction "2_2") (pintype "passive"))
    )
    (net (code "32") (name "Net-(Q5-E)") (class "Default")
      (node (ref "D14") (pin "C") (pinfunction "C_C") (pintype "passive"))
      (node (ref "Q5") (pin "1") (pinfunction "E_1") (pintype "passive"))
    )
    (net (code "33") (name "Net-(Q6-B)") (class "Default")
      (node (ref "C3") (pin "1") (pinfunction "1_1") (pintype "passive"))
      (node (ref "D17") (pin "C") (pinfunction "C_C") (pintype "passive"))
      (node (ref "Q6") (pin "2") (pinfunction "B_2") (pintype "passive"))
      (node (ref "R9") (pin "1") (pinfunction "1_1") (pintype "passive"))
    )
    (net (code "34") (name "Net-(Q6-C)") (class "Default")
      (node (ref "C3") (pin "2") (pinfunction "2_2") (pintype "passive"))
      (node (ref "Q6") (pin "3") (pinfunction "C_3") (pintype "passive"))
      (node (ref "R10") (pin "1") (pinfunction "1_1") (pintype "passive"))
    )
    (net (code "35") (name "Net-(Q7-B)") (class "Default")
      (node (ref "D15") (pin "A") (pinfunction "A_A") (pintype "passive"))
      (node (ref "Q7") (pin "2") (pinfunction "B_2") (pintype "passive"))
      (node (ref "R8") (pin "1") (pinfunction "1_1") (pintype "passive"))
    )
    (net (code "36") (name "Net-(Q7-C)") (class "Default")
      (node (ref "D18") (pin "C") (pinfunction "C_C") (pintype "passive"))
      (node (ref "Q7") (pin "3") (pinfunction "C_3") (pintype "passive"))
      (node (ref "U$2") (pin "AJ2") (pinfunction "1_AJ2") (pintype "bidirectional"))
    )
    (net (code "37") (name "Net-(Q8-B)") (class "Default")
      (node (ref "D19") (pin "C") (pinfunction "C_C") (pintype "passive"))
      (node (ref "D20") (pin "C") (pinfunction "C_C") (pintype "passive"))
      (node (ref "D21") (pin "C") (pinfunction "C_C") (pintype "passive"))
      (node (ref "Q8") (pin "2") (pinfunction "B_2") (pintype "passive"))
      (node (ref "R13") (pin "2") (pinfunction "2_2") (pintype "passive"))
    )
    (net (code "38") (name "Net-(Q8-C)") (class "Default")
      (node (ref "Q8") (pin "3") (pinfunction "C_3") (pintype "passive"))
      (node (ref "R15") (pin "2") (pinfunction "2_2") (pintype "passive"))
    )
    (net (code "39") (name "Net-(Q8-E)") (class "Default")
      (node (ref "D24") (pin "C") (pinfunction "C_C") (pintype "passive"))
      (node (ref "Q8") (pin "1") (pinfunction "E_1") (pintype "passive"))
    )
    (net (code "40") (name "Net-(Q9-B)") (class "Default")
      (node (ref "C4") (pin "1") (pinfunction "1_1") (pintype "passive"))
      (node (ref "D23") (pin "C") (pinfunction "C_C") (pintype "passive"))
      (node (ref "Q9") (pin "2") (pinfunction "B_2") (pintype "passive"))
      (node (ref "R18") (pin "1") (pinfunction "1_1") (pintype "passive"))
    )
    (net (code "41") (name "Net-(Q9-C)") (class "Default")
      (node (ref "C4") (pin "2") (pinfunction "2_2") (pintype "passive"))
      (node (ref "Q9") (pin "3") (pinfunction "C_3") (pintype "passive"))
      (node (ref "R19") (pin "1") (pinfunction "1_1") (pintype "passive"))
    )
    (net (code "42") (name "Net-(Q10-B)") (class "Default")
      (node (ref "D25") (pin "A") (pinfunction "A_A") (pintype "passive"))
      (node (ref "Q10") (pin "2") (pinfunction "B_2") (pintype "passive"))
      (node (ref "R17") (pin "1") (pinfunction "1_1") (pintype "passive"))
    )
    (net (code "43") (name "Net-(Q10-C)") (class "Default")
      (node (ref "D27") (pin "C") (pinfunction "C_C") (pintype "passive"))
      (node (ref "Q10") (pin "3") (pinfunction "C_3") (pintype "passive"))
      (node (ref "U$2") (pin "AM2") (pinfunction "1_AM2") (pintype "bidirectional"))
    )
    (net (code "44") (name "Net-(Q11-B)") (class "Default")
      (node (ref "D28") (pin "C") (pinfunction "C_C") (pintype "passive"))
      (node (ref "D29") (pin "C") (pinfunction "C_C") (pintype "passive"))
      (node (ref "D30") (pin "C") (pinfunction "C_C") (pintype "passive"))
      (node (ref "Q11") (pin "2") (pinfunction "B_2") (pintype "passive"))
      (node (ref "R21") (pin "2") (pinfunction "2_2") (pintype "passive"))
    )
    (net (code "45") (name "Net-(Q11-C)") (class "Default")
      (node (ref "Q11") (pin "3") (pinfunction "C_3") (pintype "passive"))
      (node (ref "R22") (pin "2") (pinfunction "2_2") (pintype "passive"))
    )
    (net (code "46") (name "Net-(Q11-E)") (class "Default")
      (node (ref "D33") (pin "C") (pinfunction "C_C") (pintype "passive"))
      (node (ref "Q11") (pin "1") (pinfunction "E_1") (pintype "passive"))
    )
    (net (code "47") (name "Net-(Q12-B)") (class "Default")
      (node (ref "C5") (pin "1") (pinfunction "1_1") (pintype "passive"))
      (node (ref "D32") (pin "C") (pinfunction "C_C") (pintype "passive"))
      (node (ref "Q12") (pin "2") (pinfunction "B_2") (pintype "passive"))
      (node (ref "R24") (pin "1") (pinfunction "1_1") (pintype "passive"))
    )
    (net (code "48") (name "Net-(Q12-C)") (class "Default")
      (node (ref "C5") (pin "2") (pinfunction "2_2") (pintype "passive"))
      (node (ref "Q12") (pin "3") (pinfunction "C_3") (pintype "passive"))
      (node (ref "R25") (pin "1") (pinfunction "1_1") (pintype "passive"))
    )
    (net (code "49") (name "Net-(Q13-B)") (class "Default")
      (node (ref "D34") (pin "A") (pinfunction "A_A") (pintype "passive"))
      (node (ref "Q13") (pin "2") (pinfunction "B_2") (pintype "passive"))
      (node (ref "R23") (pin "1") (pinfunction "1_1") (pintype "passive"))
    )
    (net (code "50") (name "Net-(Q13-C)") (class "Default")
      (node (ref "D36") (pin "C") (pinfunction "C_C") (pintype "passive"))
      (node (ref "Q13") (pin "3") (pinfunction "C_3") (pintype "passive"))
      (node (ref "U$2") (pin "AR2") (pinfunction "1_AR2") (pintype "bidirectional"))
    )
    (net (code "51") (name "Net-(Q14-B)") (class "Default")
      (node (ref "D37") (pin "C") (pinfunction "C_C") (pintype "passive"))
      (node (ref "D38") (pin "C") (pinfunction "C_C") (pintype "passive"))
      (node (ref "D39") (pin "C") (pinfunction "C_C") (pintype "passive"))
      (node (ref "Q14") (pin "2") (pinfunction "B_2") (pintype "passive"))
      (node (ref "R26") (pin "2") (pinfunction "2_2") (pintype "passive"))
    )
    (net (code "52") (name "Net-(Q14-C)") (class "Default")
      (node (ref "Q14") (pin "3") (pinfunction "C_3") (pintype "passive"))
      (node (ref "R27") (pin "2") (pinfunction "2_2") (pintype "passive"))
    )
    (net (code "53") (name "Net-(Q14-E)") (class "Default")
      (node (ref "D42") (pin "C") (pinfunction "C_C") (pintype "passive"))
      (node (ref "Q14") (pin "1") (pinfunction "E_1") (pintype "passive"))
    )
    (net (code "54") (name "Net-(Q15-B)") (class "Default")
      (node (ref "C6") (pin "1") (pinfunction "1_1") (pintype "passive"))
      (node (ref "D41") (pin "C") (pinfunction "C_C") (pintype "passive"))
      (node (ref "Q15") (pin "2") (pinfunction "B_2") (pintype "passive"))
      (node (ref "R29") (pin "1") (pinfunction "1_1") (pintype "passive"))
    )
    (net (code "55") (name "Net-(Q15-C)") (class "Default")
      (node (ref "C6") (pin "2") (pinfunction "2_2") (pintype "passive"))
      (node (ref "Q15") (pin "3") (pinfunction "C_3") (pintype "passive"))
      (node (ref "R30") (pin "1") (pinfunction "1_1") (pintype "passive"))
    )
    (net (code "56") (name "Net-(Q16-B)") (class "Default")
      (node (ref "D43") (pin "A") (pinfunction "A_A") (pintype "passive"))
      (node (ref "Q16") (pin "2") (pinfunction "B_2") (pintype "passive"))
      (node (ref "R28") (pin "1") (pinfunction "1_1") (pintype "passive"))
    )
    (net (code "57") (name "Net-(Q16-C)") (class "Default")
      (node (ref "D45") (pin "C") (pinfunction "C_C") (pintype "passive"))
      (node (ref "Q16") (pin "3") (pinfunction "C_3") (pintype "passive"))
      (node (ref "U$2") (pin "AU2") (pinfunction "1_AU2") (pintype "bidirectional"))
    )
    (net (code "58") (name "Net-(Q17-B)") (class "Default")
      (node (ref "D46") (pin "C") (pinfunction "C_C") (pintype "passive"))
      (node (ref "D47") (pin "C") (pinfunction "C_C") (pintype "passive"))
      (node (ref "D48") (pin "C") (pinfunction "C_C") (pintype "passive"))
      (node (ref "Q17") (pin "2") (pinfunction "B_2") (pintype "passive"))
      (node (ref "R31") (pin "2") (pinfunction "2_2") (pintype "passive"))
    )
    (net (code "59") (name "Net-(Q17-C)") (class "Default")
      (node (ref "Q17") (pin "3") (pinfunction "C_3") (pintype "passive"))
      (node (ref "R32") (pin "2") (pinfunction "2_2") (pintype "passive"))
    )
    (net (code "60") (name "Net-(Q17-E)") (class "Default")
      (node (ref "D51") (pin "C") (pinfunction "C_C") (pintype "passive"))
      (node (ref "Q17") (pin "1") (pinfunction "E_1") (pintype "passive"))
    )
    (net (code "61") (name "Net-(Q18-B)") (class "Default")
      (node (ref "C7") (pin "1") (pinfunction "1_1") (pintype "passive"))
      (node (ref "D50") (pin "C") (pinfunction "C_C") (pintype "passive"))
      (node (ref "Q18") (pin "2") (pinfunction "B_2") (pintype "passive"))
      (node (ref "R34") (pin "1") (pinfunction "1_1") (pintype "passive"))
    )
    (net (code "62") (name "Net-(Q18-C)") (class "Default")
      (node (ref "C7") (pin "2") (pinfunction "2_2") (pintype "passive"))
      (node (ref "Q18") (pin "3") (pinfunction "C_3") (pintype "passive"))
      (node (ref "R35") (pin "1") (pinfunction "1_1") (pintype "passive"))
    )
    (net (code "63") (name "Net-(Q19-B)") (class "Default")
      (node (ref "D52") (pin "A") (pinfunction "A_A") (pintype "passive"))
      (node (ref "Q19") (pin "2") (pinfunction "B_2") (pintype "passive"))
      (node (ref "R33") (pin "1") (pinfunction "1_1") (pintype "passive"))
    )
    (net (code "64") (name "Net-(Q19-C)") (class "Default")
      (node (ref "D54") (pin "C") (pinfunction "C_C") (pintype "passive"))
      (node (ref "Q19") (pin "3") (pinfunction "C_3") (pintype "passive"))
      (node (ref "U$2") (pin "BE2") (pinfunction "1_BE2") (pintype "bidirectional"))
    )
    (net (code "65") (name "Net-(Q20-B)") (class "Default")
      (node (ref "D55") (pin "C") (pinfunction "C_C") (pintype "passive"))
      (node (ref "D56") (pin "C") (pinfunction "C_C") (pintype "passive"))
      (node (ref "D57") (pin "C") (pinfunction "C_C") (pintype "passive"))
      (node (ref "Q20") (pin "2") (pinfunction "B_2") (pintype "passive"))
      (node (ref "R36") (pin "2") (pinfunction "2_2") (pintype "passive"))
    )
    (net (code "66") (name "Net-(Q20-C)") (class "Default")
      (node (ref "Q20") (pin "3") (pinfunction "C_3") (pintype "passive"))
      (node (ref "R37") (pin "2") (pinfunction "2_2") (pintype "passive"))
    )
    (net (code "67") (name "Net-(Q20-E)") (class "Default")
      (node (ref "D60") (pin "C") (pinfunction "C_C") (pintype "passive"))
      (node (ref "Q20") (pin "1") (pinfunction "E_1") (pintype "passive"))
    )
    (net (code "68") (name "Net-(Q21-B)") (class "Default")
      (node (ref "C8") (pin "1") (pinfunction "1_1") (pintype "passive"))
      (node (ref "D59") (pin "C") (pinfunction "C_C") (pintype "passive"))
      (node (ref "Q21") (pin "2") (pinfunction "B_2") (pintype "passive"))
      (node (ref "R39") (pin "1") (pinfunction "1_1") (pintype "passive"))
    )
    (net (code "69") (name "Net-(Q21-C)") (class "Default")
      (node (ref "C8") (pin "2") (pinfunction "2_2") (pintype "passive"))
      (node (ref "Q21") (pin "3") (pinfunction "C_3") (pintype "passive"))
      (node (ref "R40") (pin "1") (pinfunction "1_1") (pintype "passive"))
    )
    (net (code "70") (name "Net-(Q22-B)") (class "Default")
      (node (ref "D61") (pin "A") (pinfunction "A_A") (pintype "passive"))
      (node (ref "Q22") (pin "2") (pinfunction "B_2") (pintype "passive"))
      (node (ref "R38") (pin "1") (pinfunction "1_1") (pintype "passive"))
    )
    (net (code "71") (name "Net-(Q22-C)") (class "Default")
      (node (ref "D63") (pin "C") (pinfunction "C_C") (pintype "passive"))
      (node (ref "Q22") (pin "3") (pinfunction "C_3") (pintype "passive"))
      (node (ref "U$2") (pin "BJ2") (pinfunction "1_BJ2") (pintype "bidirectional"))
    )
    (net (code "72") (name "Net-(Q23-B)") (class "Default")
      (node (ref "D64") (pin "C") (pinfunction "C_C") (pintype "passive"))
      (node (ref "D65") (pin "C") (pinfunction "C_C") (pintype "passive"))
      (node (ref "D66") (pin "C") (pinfunction "C_C") (pintype "passive"))
      (node (ref "Q23") (pin "2") (pinfunction "B_2") (pintype "passive"))
      (node (ref "R41") (pin "2") (pinfunction "2_2") (pintype "passive"))
    )
    (net (code "73") (name "Net-(Q23-C)") (class "Default")
      (node (ref "Q23") (pin "3") (pinfunction "C_3") (pintype "passive"))
      (node (ref "R42") (pin "2") (pinfunction "2_2") (pintype "passive"))
    )
    (net (code "74") (name "Net-(Q23-E)") (class "Default")
      (node (ref "D69") (pin "C") (pinfunction "C_C") (pintype "passive"))
      (node (ref "Q23") (pin "1") (pinfunction "E_1") (pintype "passive"))
    )
    (net (code "75") (name "Net-(Q24-B)") (class "Default")
      (node (ref "C9") (pin "1") (pinfunction "1_1") (pintype "passive"))
      (node (ref "D68") (pin "C") (pinfunction "C_C") (pintype "passive"))
      (node (ref "Q24") (pin "2") (pinfunction "B_2") (pintype "passive"))
      (node (ref "R44") (pin "1") (pinfunction "1_1") (pintype "passive"))
    )
    (net (code "76") (name "Net-(Q24-C)") (class "Default")
      (node (ref "C9") (pin "2") (pinfunction "2_2") (pintype "passive"))
      (node (ref "Q24") (pin "3") (pinfunction "C_3") (pintype "passive"))
      (node (ref "R45") (pin "1") (pinfunction "1_1") (pintype "passive"))
    )
    (net (code "77") (name "Net-(Q25-B)") (class "Default")
      (node (ref "D70") (pin "A") (pinfunction "A_A") (pintype "passive"))
      (node (ref "Q25") (pin "2") (pinfunction "B_2") (pintype "passive"))
      (node (ref "R43") (pin "1") (pinfunction "1_1") (pintype "passive"))
    )
    (net (code "78") (name "Net-(Q25-C)") (class "Default")
      (node (ref "D72") (pin "C") (pinfunction "C_C") (pintype "passive"))
      (node (ref "Q25") (pin "3") (pinfunction "C_3") (pintype "passive"))
      (node (ref "U$2") (pin "BM2") (pinfunction "1_BM2") (pintype "bidirectional"))
    )
    (net (code "79") (name "Net-(R12-Pad1)") (class "Default")
      (node (ref "R12") (pin "1") (pinfunction "1_1") (pintype "passive"))
      (node (ref "R14") (pin "2") (pinfunction "2_2") (pintype "passive"))
    )
    (net (code "80") (name "Net-(R14-Pad1)") (class "Default")
      (node (ref "R14") (pin "1") (pinfunction "1_1") (pintype "passive"))
      (node (ref "R16") (pin "2") (pinfunction "2_2") (pintype "passive"))
    )
    (net (code "81") (name "Net-(R16-Pad1)") (class "Default")
      (node (ref "R16") (pin "1") (pinfunction "1_1") (pintype "passive"))
      (node (ref "R20") (pin "2") (pinfunction "2_2") (pintype "passive"))
    )
    (net (code "82") (name "Net-(U$2AD-1)") (class "Default")
      (node (ref "R25") (pin "2") (pinfunction "2_2") (pintype "passive"))
      (node (ref "U$2") (pin "AS2") (pinfunction "1_AS2") (pintype "bidirectional"))
    )
    (net (code "83") (name "Net-(U$2AF-1)") (class "Default")
      (node (ref "D37") (pin "A") (pinfunction "A_A") (pintype "passive"))
      (node (ref "U$2") (pin "AT2") (pinfunction "1_AT2") (pintype "bidirectional"))
    )
    (net (code "84") (name "Net-(U$2AJ-1)") (class "Default")
      (node (ref "R30") (pin "2") (pinfunction "2_2") (pintype "passive"))
      (node (ref "U$2") (pin "AV2") (pinfunction "1_AV2") (pintype "bidirectional"))
    )
    (net (code "85") (name "Net-(U$2AR-1)") (class "Default")
      (node (ref "D46") (pin "A") (pinfunction "A_A") (pintype "passive"))
      (node (ref "U$2") (pin "BD2") (pinfunction "1_BD2") (pintype "bidirectional"))
    )
    (net (code "86") (name "Net-(U$2AV-1)") (class "Default")
      (node (ref "R35") (pin "2") (pinfunction "2_2") (pintype "passive"))
      (node (ref "U$2") (pin "BF2") (pinfunction "1_BF2") (pintype "bidirectional"))
    )
    (net (code "87") (name "Net-(U$2AX-1)") (class "Default")
      (node (ref "D55") (pin "A") (pinfunction "A_A") (pintype "passive"))
      (node (ref "U$2") (pin "BH2") (pinfunction "1_BH2") (pintype "bidirectional"))
    )
    (net (code "88") (name "Net-(U$2BB-1)") (class "Default")
      (node (ref "R40") (pin "2") (pinfunction "2_2") (pintype "passive"))
      (node (ref "U$2") (pin "BK2") (pinfunction "1_BK2") (pintype "bidirectional"))
    )
    (net (code "89") (name "Net-(U$2BD-1)") (class "Default")
      (node (ref "D64") (pin "A") (pinfunction "A_A") (pintype "passive"))
      (node (ref "U$2") (pin "BL2") (pinfunction "1_BL2") (pintype "bidirectional"))
    )
    (net (code "90") (name "Net-(U$2BH-1)") (class "Default")
      (node (ref "R45") (pin "2") (pinfunction "2_2") (pintype "passive"))
      (node (ref "U$2") (pin "BN2") (pinfunction "1_BN2") (pintype "bidirectional"))
    )
    (net (code "91") (name "Net-(U$2BJ-1)") (class "Default")
      (node (ref "D21") (pin "A") (pinfunction "A_A") (pintype "passive"))
      (node (ref "D3") (pin "A") (pinfunction "A_A") (pintype "passive"))
      (node (ref "D39") (pin "A") (pinfunction "A_A") (pintype "passive"))
      (node (ref "D57") (pin "A") (pinfunction "A_A") (pintype "passive"))
      (node (ref "U$2") (pin "BP2") (pinfunction "1_BP2") (pintype "bidirectional"))
    )
    (net (code "92") (name "Net-(U$2BL-1)") (class "Default")
      (node (ref "D12") (pin "A") (pinfunction "A_A") (pintype "passive"))
      (node (ref "D30") (pin "A") (pinfunction "A_A") (pintype "passive"))
      (node (ref "D48") (pin "A") (pinfunction "A_A") (pintype "passive"))
      (node (ref "D66") (pin "A") (pinfunction "A_A") (pintype "passive"))
      (node (ref "U$2") (pin "BR2") (pinfunction "1_BR2") (pintype "bidirectional"))
    )
    (net (code "93") (name "Net-(U$2BN-1)") (class "Default")
      (node (ref "D11") (pin "A") (pinfunction "A_A") (pintype "passive"))
      (node (ref "D2") (pin "A") (pinfunction "A_A") (pintype "passive"))
      (node (ref "D38") (pin "A") (pinfunction "A_A") (pintype "passive"))
      (node (ref "D47") (pin "A") (pinfunction "A_A") (pintype "passive"))
      (node (ref "U$2") (pin "BS2") (pinfunction "1_BS2") (pintype "bidirectional"))
    )
    (net (code "94") (name "Net-(U$2BP-1)") (class "Default")
      (node (ref "D20") (pin "A") (pinfunction "A_A") (pintype "passive"))
      (node (ref "D29") (pin "A") (pinfunction "A_A") (pintype "passive"))
      (node (ref "D56") (pin "A") (pinfunction "A_A") (pintype "passive"))
      (node (ref "D65") (pin "A") (pinfunction "A_A") (pintype "passive"))
      (node (ref "U$2") (pin "BT2") (pinfunction "1_BT2") (pintype "bidirectional"))
    )
    (net (code "95") (name "Net-(U$2BR-1)") (class "Default")
      (node (ref "D16") (pin "A") (pinfunction "A_A") (pintype "passive"))
      (node (ref "D26") (pin "A") (pinfunction "A_A") (pintype "passive"))
      (node (ref "D35") (pin "A") (pinfunction "A_A") (pintype "passive"))
      (node (ref "D44") (pin "A") (pinfunction "A_A") (pintype "passive"))
      (node (ref "D53") (pin "A") (pinfunction "A_A") (pintype "passive"))
      (node (ref "D6") (pin "A") (pinfunction "A_A") (pintype "passive"))
      (node (ref "D62") (pin "A") (pinfunction "A_A") (pintype "passive"))
      (node (ref "D71") (pin "A") (pinfunction "A_A") (pintype "passive"))
      (node (ref "U$2") (pin "BU2") (pinfunction "1_BU2") (pintype "bidirectional"))
    )
    (net (code "96") (name "Net-(U$2BT-1)") (class "Default")
      (node (ref "R20") (pin "1") (pinfunction "1_1") (pintype "passive"))
      (node (ref "U$2") (pin "BV2") (pinfunction "1_BV2") (pintype "bidirectional"))
    )
    (net (code "97") (name "Net-(U$2H-1)") (class "Default")
      (node (ref "D1") (pin "A") (pinfunction "A_A") (pintype "passive"))
      (node (ref "U$2") (pin "AD2") (pinfunction "1_AD2") (pintype "bidirectional"))
    )
    (net (code "98") (name "Net-(U$2L-1)") (class "Default")
      (node (ref "R5") (pin "2") (pinfunction "2_2") (pintype "passive"))
      (node (ref "U$2") (pin "AF2") (pinfunction "1_AF2") (pintype "bidirectional"))
    )
    (net (code "99") (name "Net-(U$2N-1)") (class "Default")
      (node (ref "D10") (pin "A") (pinfunction "A_A") (pintype "passive"))
      (node (ref "U$2") (pin "AH2") (pinfunction "1_AH2") (pintype "bidirectional"))
    )
    (net (code "100") (name "Net-(U$2R-1)") (class "Default")
      (node (ref "R10") (pin "2") (pinfunction "2_2") (pintype "passive"))
      (node (ref "U$2") (pin "AK2") (pinfunction "1_AK2") (pintype "bidirectional"))
    )
    (net (code "101") (name "Net-(U$2T-1)") (class "Default")
      (node (ref "D19") (pin "A") (pinfunction "A_A") (pintype "passive"))
      (node (ref "U$2") (pin "AL2") (pinfunction "1_AL2") (pintype "bidirectional"))
    )
    (net (code "102") (name "Net-(U$2X-1)") (class "Default")
      (node (ref "R19") (pin "2") (pinfunction "2_2") (pintype "passive"))
      (node (ref "U$2") (pin "AN2") (pinfunction "1_AN2") (pintype "bidirectional"))
    )
    (net (code "103") (name "Net-(U$2Z-1)") (class "Default")
      (node (ref "D28") (pin "A") (pinfunction "A_A") (pintype "passive"))
      (node (ref "U$2") (pin "AP2") (pinfunction "1_AP2") (pintype "bidirectional"))
    )
  )
)
